# PSU.net
KiCad netlist of a schematic drawn in Altium Designer
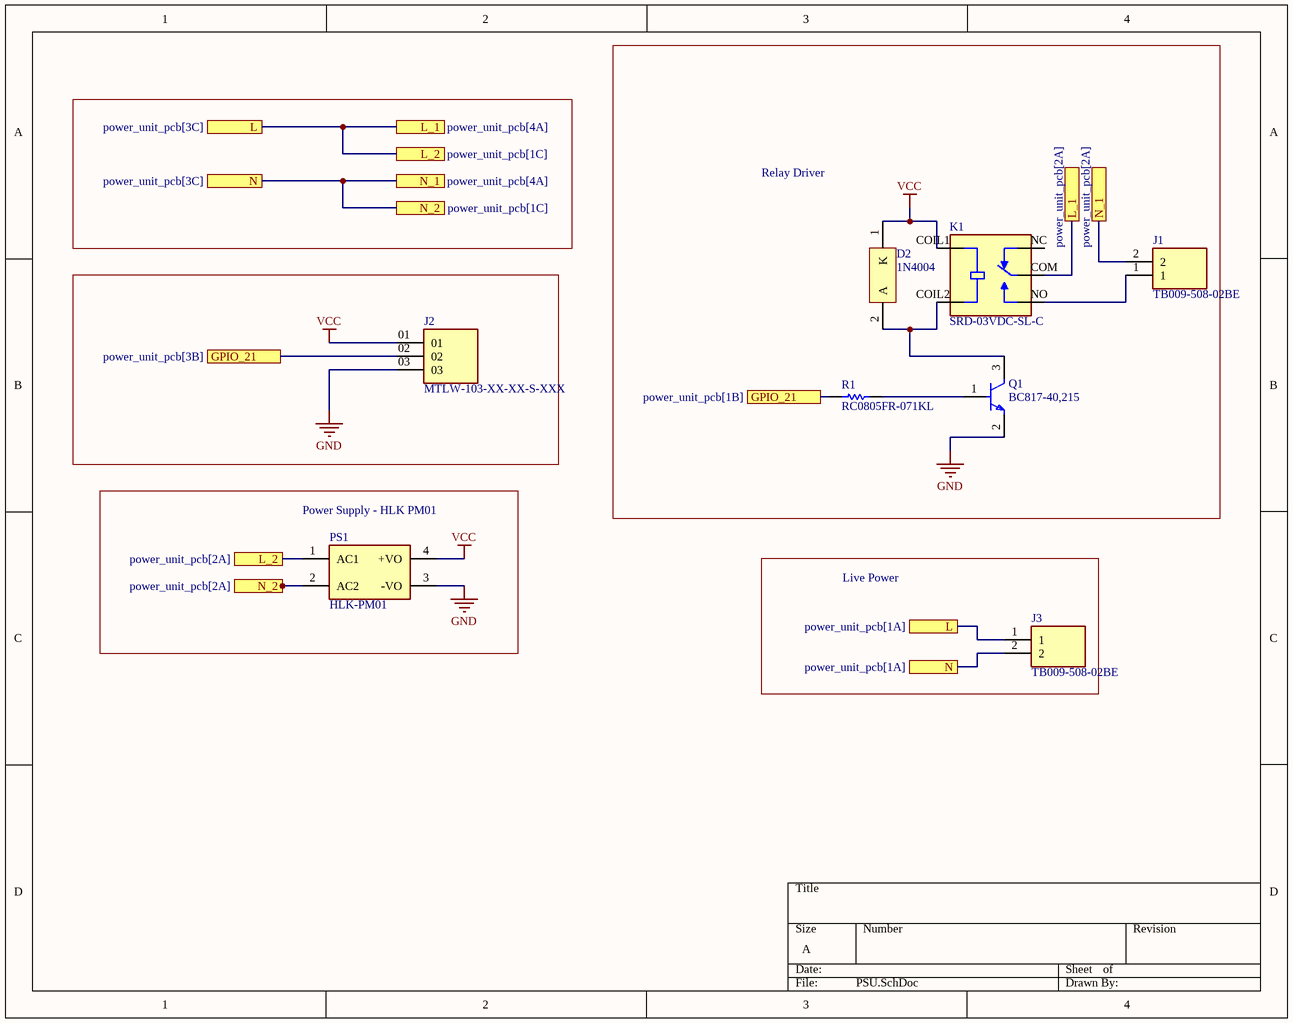
[diagram p0: PSU.SchDoc]

(export (version "E")
  (design (tool "Eeschema 10.0.6"))
  (components
    (comp (ref "D2")
      (value "1N4004")
      (footprint "ONSC-AXIAL_LEAD-2-59-10_P")
      (description "Standard Recovery Rectifier, 2-Pin Axial_Lead, Pb-Free, Bulk Bag")
      (fields (field (name "MANUFACTURER") "On Semiconductor"))
      (libsource (lib "Altium Content Vault") (part "ONSC-D-K1A2-2_A"))
    )
    (comp (ref "J1")
      (value "TB009-508-02BE")
      (footprint "CUI_TB009-508-02BE")
      (description "2~24 Poles, Screw Type, Horizontal, 5.08 Pitch, 26~12 (AWG), Terminal Block Connector")
      (fields (field (name "MF") "Same Sky"))
      (libsource (lib "") (part "CMP-002-00071-1_1"))
    )
    (comp (ref "J2")
      (value "MTLW-103-XX-XX-S-XXX")
      (footprint "SAMTEC_HTSW-103-XX-X-S")
      (description "Connector Header Through Hole 40 position 0.100\" (2.54mm)")
      (libsource (lib "power_unit_board_pcb") (part "MTLW-103-XX-XX-S-XXX"))
    )
    (comp (ref "J3")
      (value "TB009-508-02BE")
      (footprint "CUI_TB009-508-02BE")
      (description "2~24 Poles, Screw Type, Horizontal, 5.08 Pitch, 26~12 (AWG), Terminal Block Connector")
      (fields (field (name "MF") "Same Sky"))
      (libsource (lib "power_unit_board_pcb") (part "CMP-002-00071-1"))
    )
    (comp (ref "K1")
      (value "SRD-03VDC-SL-C")
      (footprint "RELAY_SRD-03VDC-SL-C")
      (description "Relays General Purpose Non Latching 3VDC SPDT 10A (250VAC) Max 5PIN")
      (fields (field (name "MF") "Songle Relay"))
      (libsource (lib "power_unit_board_pcb") (part "CMP-003-000000-1"))
    )
    (comp (ref "PS1")
      (value "HLK-PM01")
      (footprint "CONV_HLK-PM01")
      (fields
        (field (name "MP") "hlk-pm01")
        (field (name "MF") "Hi-link")
        (field (name "LCSC PART NUMBER") "C209903")
      )
      (libsource (lib "power_unit_board_pcb") (part "HLK-PM01"))
    )
    (comp (ref "Q1")
      (value "BC817-40,215")
      (footprint "FP-SOT23-IPC_A")
      (description "TRANS NPN 45V 0.5A SOT23")
      (fields
        (field (name "OCTOPART") "https://octopart.com/bc817-40%2C215-nexperia-78739081")
        (field (name "MANUFACTURER") "Nexperia")
      )
      (libsource (lib "power_unit_board_pcb") (part "BC817-40,215"))
    )
    (comp (ref "R1")
      (value "RC0805FR-071KL")
      (footprint "RESC2013X60X35ML10T20")
      (description "Chip Resistor, 1 KOhm, +/- 1%, 125 mW, -55 to 155 degC, 0805 (2012 Metric), RoHS, Tape and Reel")
      (fields (field (name "TOLERANCE") "1%") (field (name "MANUFACTURER") "Yageo"))
      (libsource (lib "Altium Content Vault") (part "RES-2"))
    )
  )
  (nets
    (net (code "1") (name "/GPIO_21") (class "Default")
      (node (ref "J2") (pin "02") (pinfunction "02_02") (pintype "passive"))
      (node (ref "R1") (pin "1") (pinfunction "1_1") (pintype "passive"))
    )
    (net (code "2") (name "/L") (class "Default")
      (node (ref "J3") (pin "1") (pinfunction "1_1") (pintype "passive"))
      (node (ref "K1") (pin "COM") (pinfunction "COM_COM") (pintype "passive"))
      (node (ref "PS1") (pin "1") (pinfunction "AC1_1") (pintype "passive"))
    )
    (net (code "3") (name "/N") (class "Default")
      (node (ref "J1") (pin "2") (pinfunction "2_2") (pintype "passive"))
      (node (ref "J3") (pin "2") (pinfunction "2_2") (pintype "passive"))
      (node (ref "PS1") (pin "2") (pinfunction "AC2_2") (pintype "passive"))
    )
    (net (code "4") (name "GND") (class "Default")
      (node (ref "J2") (pin "03") (pinfunction "03_03") (pintype "passive"))
      (node (ref "PS1") (pin "3") (pinfunction "-VO_3") (pintype "passive"))
      (node (ref "Q1") (pin "2") (pinfunction "E_2") (pintype "passive"))
    )
    (net (code "5") (name "Net-(D2-A)") (class "Default")
      (node (ref "D2") (pin "2") (pinfunction "A_2") (pintype "passive"))
      (node (ref "K1") (pin "COIL2") (pinfunction "COIL2_COIL2") (pintype "passive"))
      (node (ref "Q1") (pin "3") (pinfunction "C_3") (pintype "passive"))
    )
    (net (code "6") (name "Net-(J1-Pad1)") (class "Default")
      (node (ref "J1") (pin "1") (pinfunction "1_1") (pintype "passive"))
      (node (ref "K1") (pin "NO") (pinfunction "NO_NO") (pintype "passive"))
    )
    (net (code "7") (name "Net-(Q1-B)") (class "Default")
      (node (ref "Q1") (pin "1") (pinfunction "B_1") (pintype "passive"))
      (node (ref "R1") (pin "2") (pinfunction "2_2") (pintype "passive"))
    )
    (net (code "8") (name "VCC") (class "Default")
      (node (ref "D2") (pin "1") (pinfunction "K_1") (pintype "passive"))
      (node (ref "J2") (pin "01") (pinfunction "01_01") (pintype "passive"))
      (node (ref "K1") (pin "COIL1") (pinfunction "COIL1_COIL1") (pintype "passive"))
      (node (ref "PS1") (pin "4") (pinfunction "+VO_4") (pintype "passive"))
    )
    (net (code "9") (name "unconnected-(K1-PadNC)") (class "Default")
      (node (ref "K1") (pin "NC") (pinfunction "NC_NC") (pintype "passive"))
    )
  )
)
